# Sheet1.net
KiCad netlist of a schematic drawn in Altium Designer
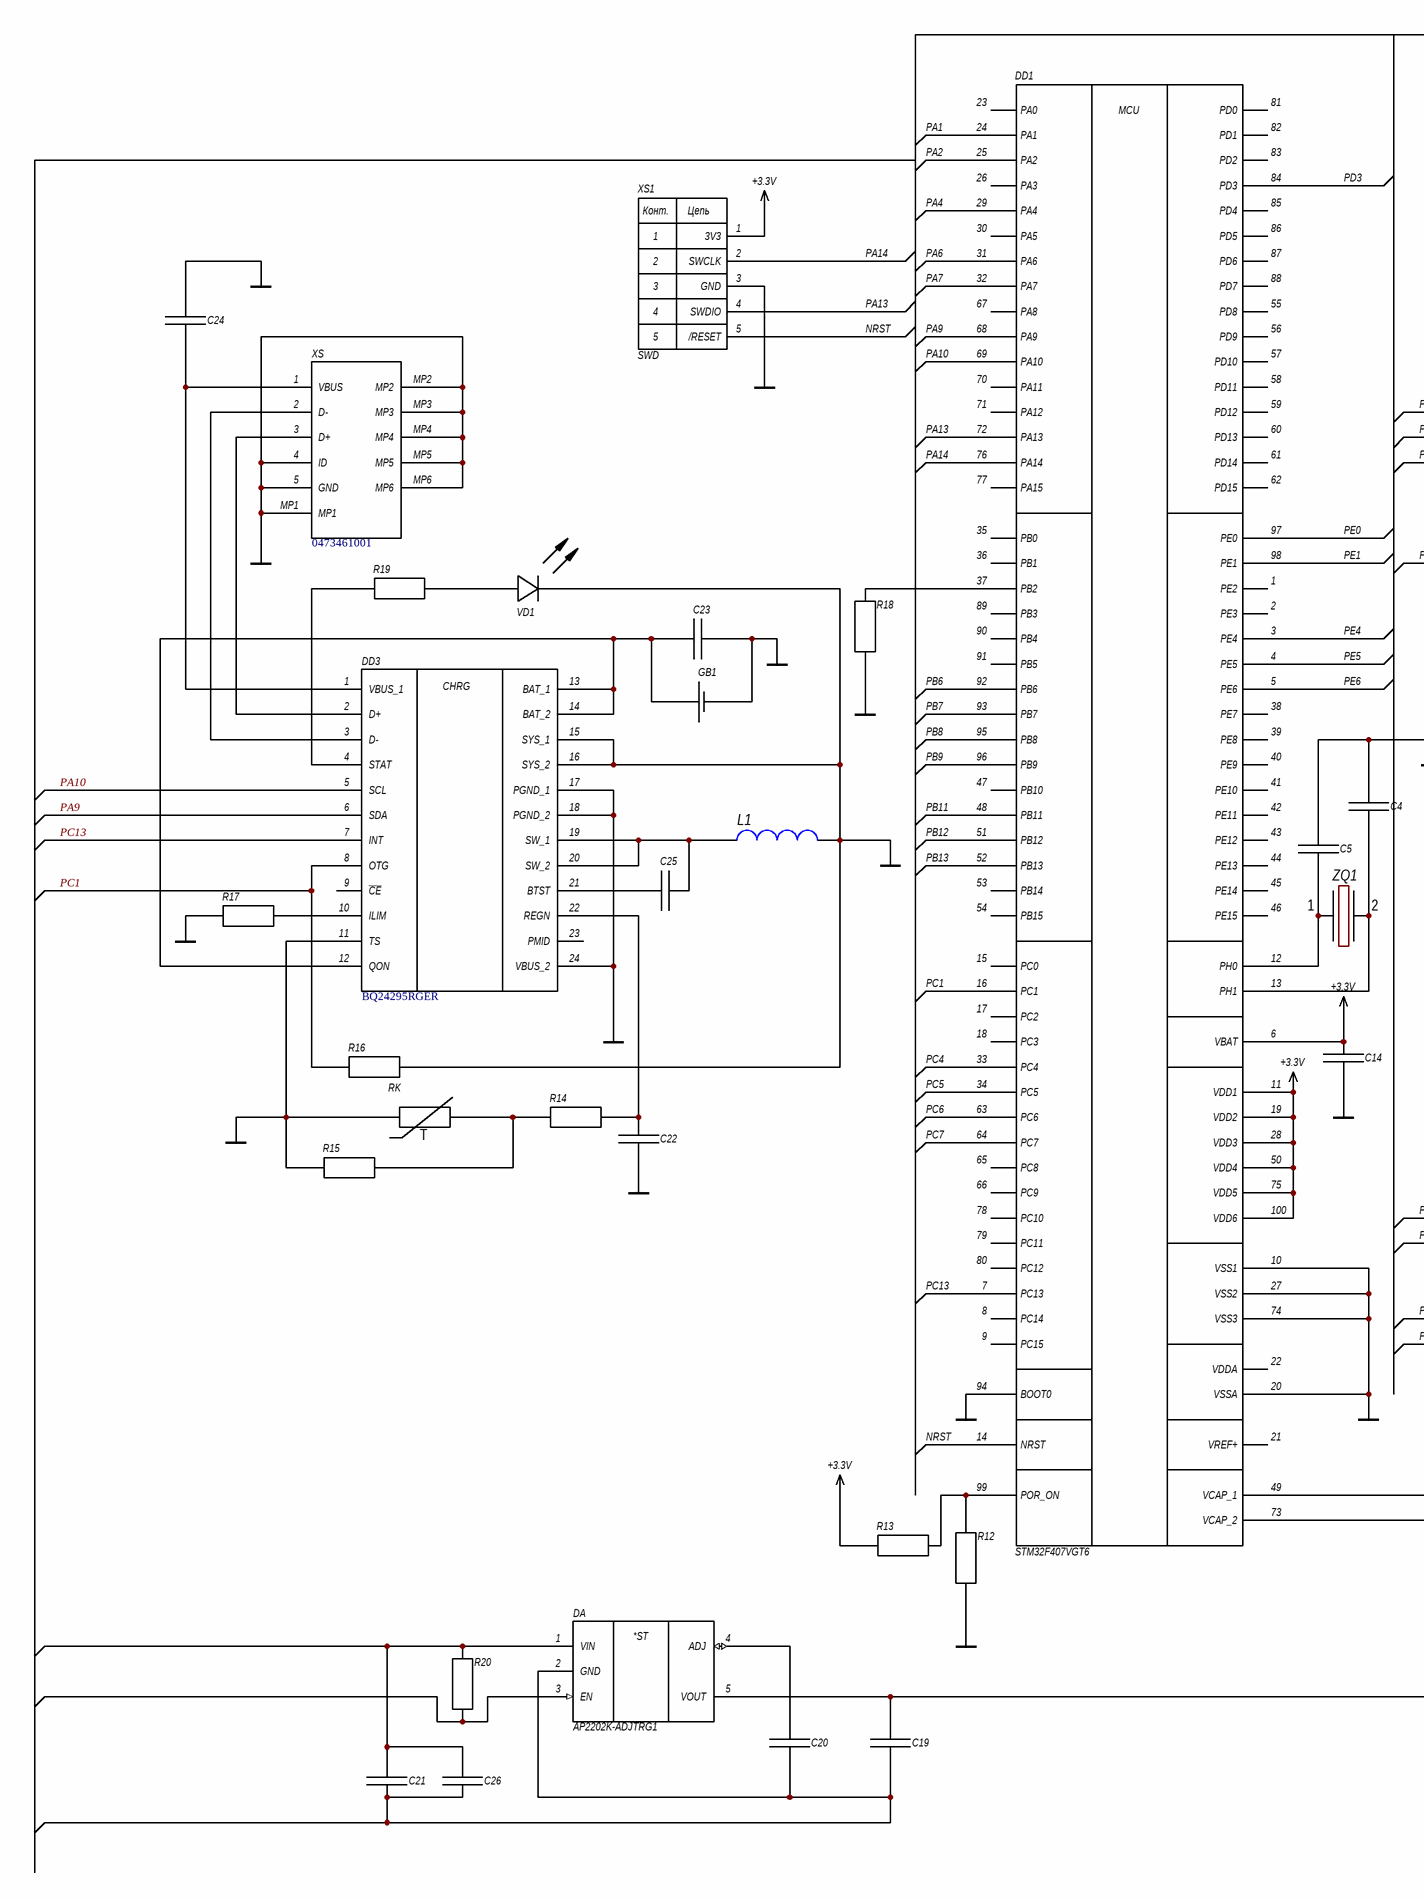
[diagram p0: Sheet1.SchDoc, left]
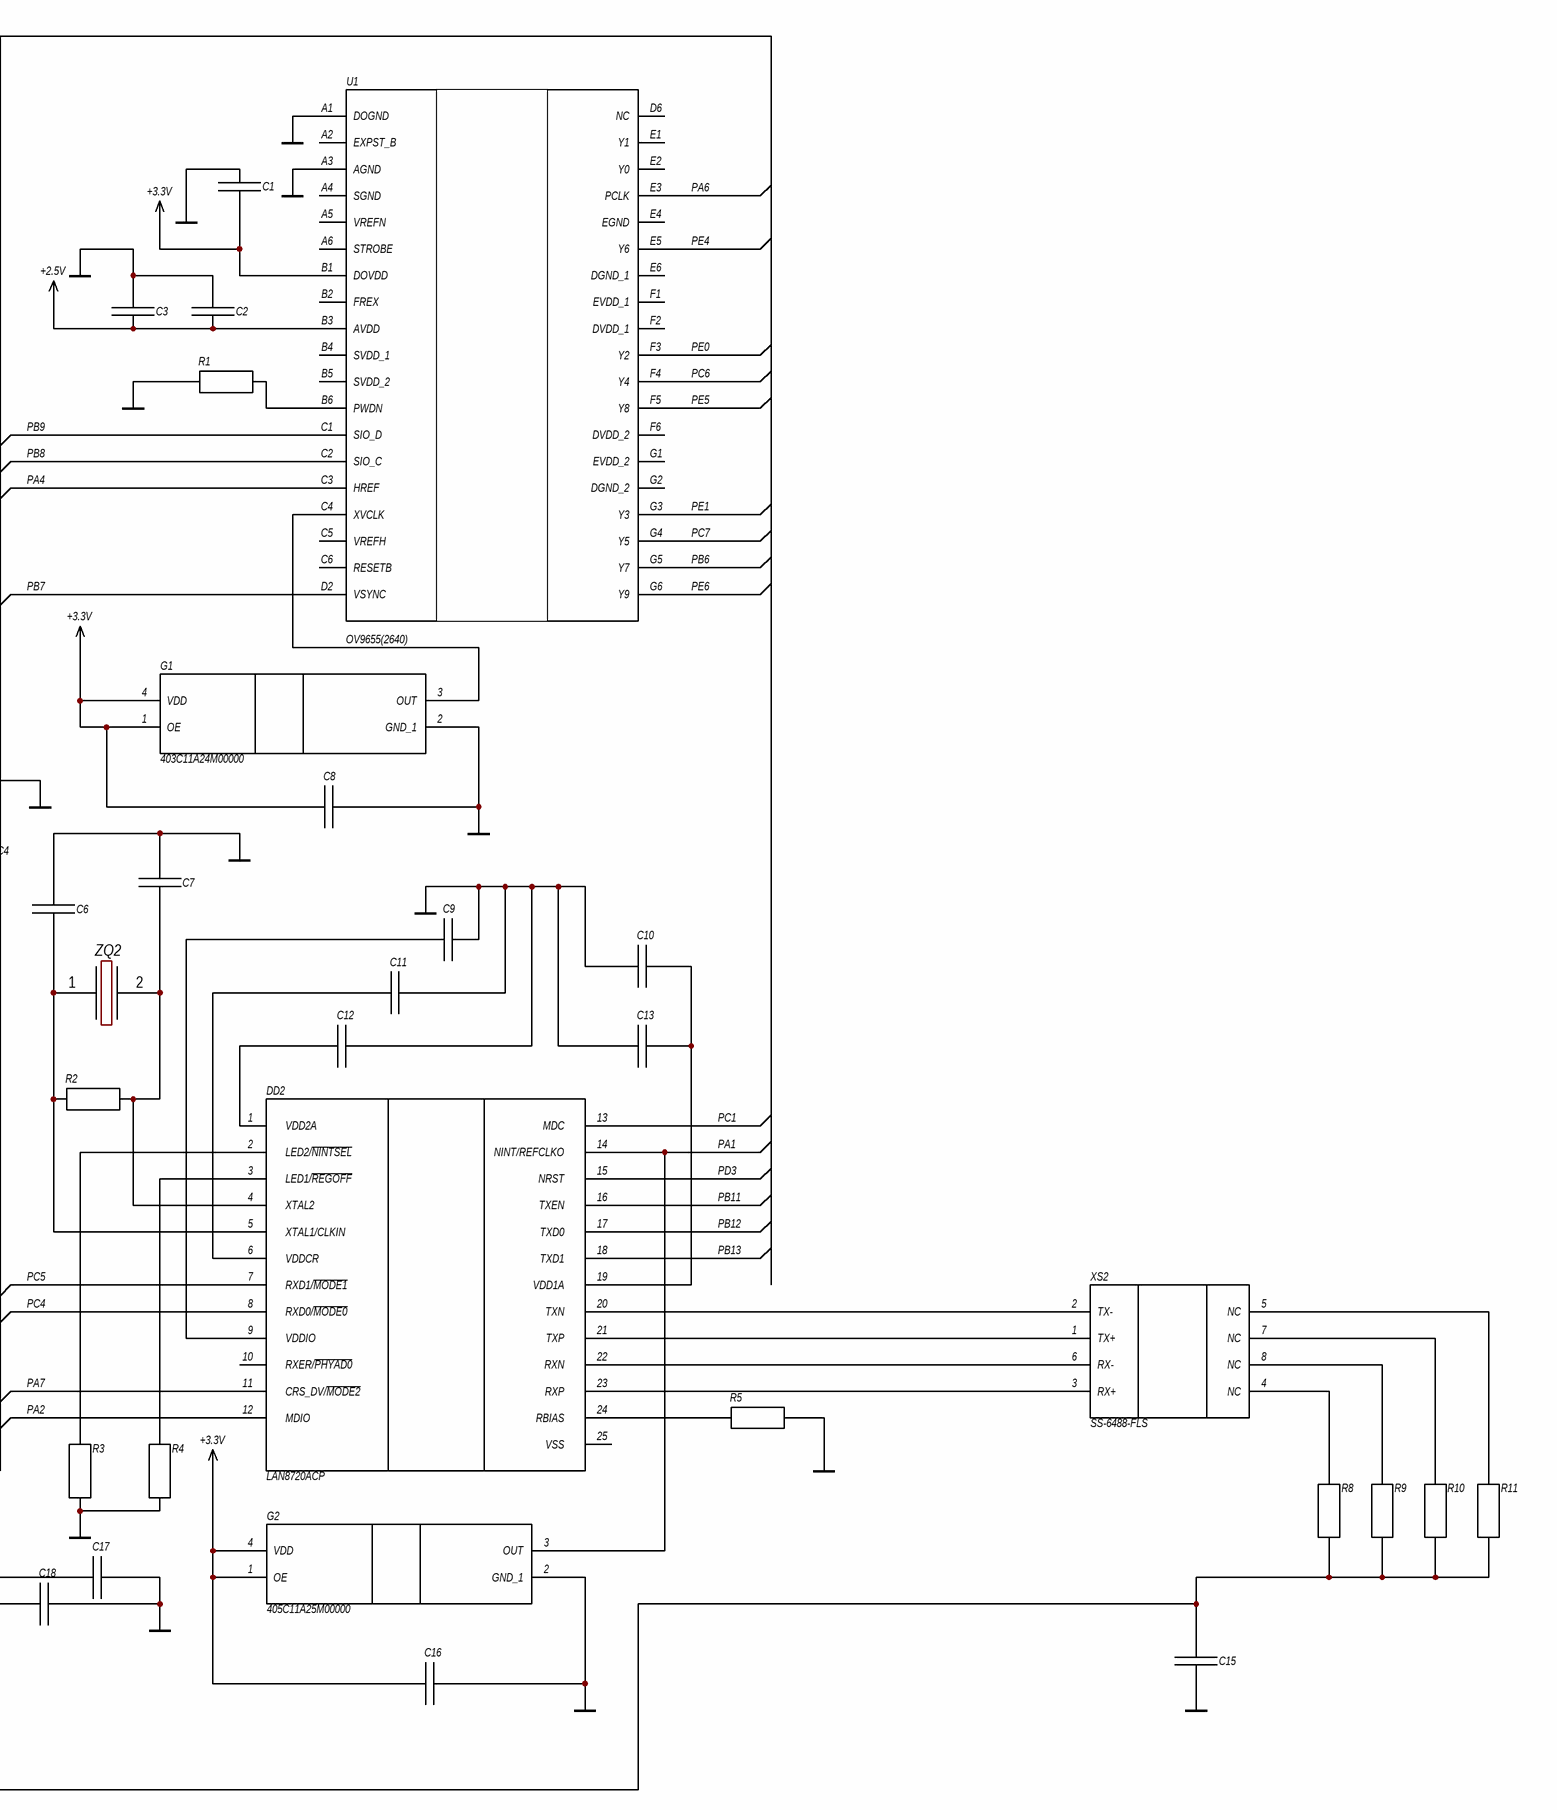
[diagram p1: Sheet1.SchDoc, right]

(export (version "E")
  (design (tool "Eeschema 10.0.6"))
  (components
    (comp (ref "C1")
      (value "~")
      (footprint "0805 (Capacitor)")
      (libsource (lib "SamacSys") (part "Condensator"))
    )
    (comp (ref "C2")
      (value "~")
      (footprint "0805 (Capacitor)")
      (libsource (lib "SamacSys") (part "Condensator"))
    )
    (comp (ref "C3")
      (value "~")
      (footprint "0805 (Capacitor)")
      (libsource (lib "SamacSys") (part "Condensator"))
    )
    (comp (ref "C4")
      (value "~")
      (footprint "0805 (Capacitor)")
      (libsource (lib "SamacSys") (part "Condensator"))
    )
    (comp (ref "C5")
      (value "~")
      (footprint "0805 (Capacitor)")
      (libsource (lib "SamacSys") (part "Condensator"))
    )
    (comp (ref "C6")
      (value "~")
      (footprint "0805 (Capacitor)")
      (libsource (lib "SamacSys") (part "Condensator"))
    )
    (comp (ref "C7")
      (value "~")
      (footprint "0805 (Capacitor)")
      (libsource (lib "SamacSys") (part "Condensator"))
    )
    (comp (ref "C8")
      (value "~")
      (footprint "0805 (Capacitor)")
      (libsource (lib "SamacSys") (part "Condensator"))
    )
    (comp (ref "C9")
      (value "~")
      (footprint "0805 (Capacitor)")
      (libsource (lib "SamacSys") (part "Condensator"))
    )
    (comp (ref "C10")
      (value "~")
      (footprint "0805 (Capacitor)")
      (libsource (lib "SamacSys") (part "Condensator"))
    )
    (comp (ref "C11")
      (value "~")
      (footprint "0805 (Capacitor)")
      (libsource (lib "SamacSys") (part "Condensator"))
    )
    (comp (ref "C12")
      (value "~")
      (footprint "0805 (Capacitor)")
      (libsource (lib "SamacSys") (part "Condensator"))
    )
    (comp (ref "C13")
      (value "~")
      (footprint "0805 (Capacitor)")
      (libsource (lib "SamacSys") (part "Condensator"))
    )
    (comp (ref "C14")
      (value "~")
      (footprint "0805 (Capacitor)")
      (libsource (lib "SamacSys") (part "Condensator"))
    )
    (comp (ref "C15")
      (value "~")
      (footprint "0805 (Capacitor)")
      (libsource (lib "SamacSys") (part "Condensator"))
    )
    (comp (ref "C16")
      (value "~")
      (footprint "0805 (Capacitor)")
      (libsource (lib "SamacSys") (part "Condensator"))
    )
    (comp (ref "C17")
      (value "~")
      (footprint "0805 (Capacitor)")
      (libsource (lib "SamacSys") (part "Condensator"))
    )
    (comp (ref "C18")
      (value "~")
      (footprint "0805 (Capacitor)")
      (libsource (lib "SamacSys") (part "Condensator"))
    )
    (comp (ref "C19")
      (value "~")
      (footprint "0805 (Capacitor)")
      (libsource (lib "SamacSys") (part "Condensator"))
    )
    (comp (ref "C20")
      (value "~")
      (footprint "0805 (Capacitor)")
      (libsource (lib "SamacSys") (part "Condensator"))
    )
    (comp (ref "C21")
      (value "~")
      (footprint "0805 (Capacitor)")
      (libsource (lib "SamacSys") (part "Condensator"))
    )
    (comp (ref "C22")
      (value "~")
      (footprint "0805 (Capacitor)")
      (libsource (lib "SamacSys") (part "Condensator"))
    )
    (comp (ref "C23")
      (value "~")
      (footprint "0805 (Capacitor)")
      (libsource (lib "SamacSys") (part "Condensator"))
    )
    (comp (ref "C24")
      (value "~")
      (footprint "0805 (Capacitor)")
      (libsource (lib "SamacSys") (part "Condensator"))
    )
    (comp (ref "C25")
      (value "~")
      (footprint "0805 (Capacitor)")
      (libsource (lib "SamacSys") (part "Condensator"))
    )
    (comp (ref "C26")
      (value "~")
      (footprint "0805 (Capacitor)")
      (libsource (lib "SamacSys") (part "Condensator"))
    )
    (comp (ref "DA")
      (value "AP2202K-ADJTRG1")
      (footprint "SOT95P280X145-5N")
      (description "Power Supply")
      (fields (field (name "MOUSER PART NUMBER") "621-AP2202K-ADJTRG1"))
      (libsource (lib "SamacSys") (part "AP2202K-ADJTRG1"))
    )
    (comp (ref "DD1")
      (value "STM32F407VGT6")
      (footprint "QFP50P1600X1600X160-100N")
      (description "Integrated Circuit")
      (fields (field (name "MOUSER PART NUMBER") "511-STM32F407VGT6"))
      (libsource (lib "SamacSys") (part "STM32F407VGT6"))
    )
    (comp (ref "DD2")
      (value "LAN8720ACP")
      (footprint "SamacSys:QFN50P400X400X100-25N-D")
      (description "Integrated Circuit")
      (libsource (lib "SamacSys") (part "LAN8720ACP"))
    )
    (comp (ref "DD3")
      (value "BQ24295RGER")
      (footprint "SamacSys:QFN50P400X400X100-25N-D")
      (description "Integrated Circuit")
      (fields (field (name "MOUSER PART NUMBER") "595-BQ24295RGER"))
      (libsource (lib "SamacSys") (part "BQ24295RGER"))
    )
    (comp (ref "G1")
      (value "403C11A24M00000")
      (footprint "403C11A20M00000")
      (description "Crystal or Oscillator")
      (fields (field (name "MOUSER PART NUMBER") "774-403C11A24M00000"))
      (libsource (lib "SamacSys") (part "403C11A24M00000"))
    )
    (comp (ref "G2")
      (value "405C11A25M00000")
      (footprint "405C11A25M00000")
      (description "Crystal or Oscillator")
      (fields (field (name "MOUSER PART NUMBER") "774-405C11A25M00000"))
      (libsource (lib "SamacSys") (part "405C11A25M00000"))
    )
    (comp (ref "GB1") (value "~") (footprint "Battery") (libsource (lib "SamacSys") (part "Battery")))
    (comp (ref "L1")
      (value "~")
      (footprint "IND: SDR0604")
      (fields
        (field (name "MANUFACTURER") "Murata Electronics")
        (field (name "PARTNUMBER") "LQM18FN100M00D")
        (field (name "VALUEMANUFACTURERPARTNUMBER") "Fixed inductor, , , 0603, 50mA, -55...+125°C")
      )
      (libsource (lib "SamacSys") (part "Inductor_0603"))
    )
    (comp (ref "R1") (value "~") (footprint "0805 (Resistor)") (libsource (lib "SamacSys") (part "Resistor")))
    (comp (ref "R2") (value "~") (footprint "0805 (Resistor)") (libsource (lib "SamacSys") (part "Resistor")))
    (comp (ref "R3") (value "~") (footprint "0805 (Resistor)") (libsource (lib "SamacSys") (part "Resistor")))
    (comp (ref "R4") (value "~") (footprint "0805 (Resistor)") (libsource (lib "SamacSys") (part "Resistor")))
    (comp (ref "R5") (value "~") (footprint "0805 (Resistor)") (libsource (lib "SamacSys") (part "Resistor")))
    (comp (ref "R8") (value "~") (footprint "0805 (Resistor)") (libsource (lib "SamacSys") (part "Resistor")))
    (comp (ref "R9") (value "~") (footprint "0805 (Resistor)") (libsource (lib "SamacSys") (part "Resistor")))
    (comp (ref "R10")
      (value "~")
      (footprint "0805 (Resistor)")
      (libsource (lib "SamacSys") (part "Resistor"))
    )
    (comp (ref "R11")
      (value "~")
      (footprint "0805 (Resistor)")
      (libsource (lib "SamacSys") (part "Resistor"))
    )
    (comp (ref "R12")
      (value "~")
      (footprint "0805 (Resistor)")
      (libsource (lib "SamacSys") (part "Resistor"))
    )
    (comp (ref "R13")
      (value "~")
      (footprint "0805 (Resistor)")
      (libsource (lib "SamacSys") (part "Resistor"))
    )
    (comp (ref "R14")
      (value "~")
      (footprint "0805 (Resistor)")
      (libsource (lib "SamacSys") (part "Resistor"))
    )
    (comp (ref "R15")
      (value "~")
      (footprint "0805 (Resistor)")
      (libsource (lib "SamacSys") (part "Resistor"))
    )
    (comp (ref "R16")
      (value "~")
      (footprint "0805 (Resistor)")
      (libsource (lib "SamacSys") (part "Resistor"))
    )
    (comp (ref "R17")
      (value "~")
      (footprint "0805 (Resistor)")
      (libsource (lib "SamacSys") (part "Resistor"))
    )
    (comp (ref "R18")
      (value "~")
      (footprint "0805 (Resistor)")
      (libsource (lib "SamacSys") (part "Resistor"))
    )
    (comp (ref "R19")
      (value "~")
      (footprint "0805 (Resistor)")
      (libsource (lib "SamacSys") (part "Resistor"))
    )
    (comp (ref "R20")
      (value "~")
      (footprint "0805 (Resistor)")
      (libsource (lib "SamacSys") (part "Resistor"))
    )
    (comp (ref "RK")
      (value "~")
      (footprint "0805 (Resistor)")
      (libsource (lib "SamacSys") (part "Resistor_termo"))
    )
    (comp (ref "U1")
      (value "OV9655(2640)")
      (footprint "BGA38C80P6X7_572X628X96")
      (description "Integrated Circuit")
      (fields (field (name "MANUFACTURER_PART_NUMBER") "OV2640-VL9A"))
      (libsource (lib "SamacSys") (part "OV2640-VL9A"))
    )
    (comp (ref "VD1")
      (value "~")
      (footprint "LED")
      (fields (field (name "VALUEMANUFACTURERPARTNUMBER") "LED, Green, *, *, *, -55...+150°C"))
      (libsource (lib "SamacSys") (part "LED_single"))
    )
    (comp (ref "XS")
      (value "0473461001")
      (footprint "0473461001")
      (description "Connector")
      (libsource (lib "SamacSys") (part "0473461001"))
    )
    (comp (ref "XS1") (value "SWD") (footprint "SWD") (libsource (lib "SamacSys") (part "SWD")))
    (comp (ref "XS2")
      (value "SS-6488-FLS")
      (footprint "SamacSys:SS6488FLS")
      (description "Connector")
      (fields (field (name "MOUSER PART NUMBER") "530-SS-6488-FLS"))
      (libsource (lib "SamacSys") (part "SS-6488-FLS"))
    )
    (comp (ref "ZQ1")
      (value "~")
      (footprint "OSC: 2016")
      (fields
        (field (name "MANUFACTURER") "Murata Electronics")
        (field (name "PARTNUMBER") "XRCGB25M000F0L00R0")
        (field (name "VALUEMANUFACTURERPARTNUMBER") "Crystal, , 6pF, ±50ppm, case 2016, -30...+85°C")
      )
      (libsource (lib "SamacSys") (part "Crystal_2016"))
    )
    (comp (ref "ZQ2")
      (value "~")
      (footprint "OSC: 2016")
      (fields
        (field (name "MANUFACTURER") "Murata Electronics")
        (field (name "PARTNUMBER") "XRCGB25M000F0L00R0")
        (field (name "VALUEMANUFACTURERPARTNUMBER") "Crystal, , 6pF, ±50ppm, case 2016, -30...+85°C")
      )
      (libsource (lib "SamacSys") (part "Crystal_2016"))
    )
  )
  (nets
    (net (code "1") (name "+2.5V") (class "Default")
      (node (ref "C2") (pin "2") (pinfunction "2_2") (pintype "passive"))
      (node (ref "C3") (pin "2") (pinfunction "2_2") (pintype "passive"))
      (node (ref "U1") (pin "B3") (pinfunction "AVDD_B3") (pintype "passive"))
    )
    (net (code "2") (name "+3.3V") (class "Default")
      (node (ref "C1") (pin "2") (pinfunction "2_2") (pintype "passive"))
      (node (ref "C14") (pin "1") (pinfunction "1_1") (pintype "passive"))
      (node (ref "C16") (pin "1") (pinfunction "1_1") (pintype "passive"))
      (node (ref "C8") (pin "1") (pinfunction "1_1") (pintype "passive"))
      (node (ref "DD1") (pin "100") (pinfunction "VDD6_100") (pintype "passive"))
      (node (ref "DD1") (pin "11") (pinfunction "VDD1_11") (pintype "passive"))
      (node (ref "DD1") (pin "19") (pinfunction "VDD2_19") (pintype "passive"))
      (node (ref "DD1") (pin "28") (pinfunction "VDD3_28") (pintype "passive"))
      (node (ref "DD1") (pin "50") (pinfunction "VDD4_50") (pintype "passive"))
      (node (ref "DD1") (pin "6") (pinfunction "VBAT_6") (pintype "passive"))
      (node (ref "DD1") (pin "75") (pinfunction "VDD5_75") (pintype "passive"))
      (node (ref "G1") (pin "1") (pinfunction "OE_1") (pintype "passive"))
      (node (ref "G1") (pin "4") (pinfunction "VDD_4") (pintype "passive"))
      (node (ref "G2") (pin "1") (pinfunction "OE_1") (pintype "passive"))
      (node (ref "G2") (pin "4") (pinfunction "VDD_4") (pintype "passive"))
      (node (ref "R13") (pin "2") (pinfunction "2_2") (pintype "passive"))
      (node (ref "U1") (pin "B1") (pinfunction "DOVDD_B1") (pintype "passive"))
      (node (ref "XS1") (pin "1") (pinfunction "3V3_1") (pintype "passive"))
    )
    (net (code "3") (name "/GND") (class "Default")
      (node (ref "C1") (pin "1") (pinfunction "1_1") (pintype "passive"))
      (node (ref "C10") (pin "1") (pinfunction "1_1") (pintype "passive"))
      (node (ref "C11") (pin "2") (pinfunction "2_2") (pintype "passive"))
      (node (ref "C12") (pin "2") (pinfunction "2_2") (pintype "passive"))
      (node (ref "C13") (pin "1") (pinfunction "1_1") (pintype "passive"))
      (node (ref "C14") (pin "2") (pinfunction "2_2") (pintype "passive"))
      (node (ref "C15") (pin "1") (pinfunction "1_1") (pintype "passive"))
      (node (ref "C16") (pin "2") (pinfunction "2_2") (pintype "passive"))
      (node (ref "C17") (pin "2") (pinfunction "2_2") (pintype "passive"))
      (node (ref "C18") (pin "2") (pinfunction "2_2") (pintype "passive"))
      (node (ref "C2") (pin "1") (pinfunction "1_1") (pintype "passive"))
      (node (ref "C22") (pin "2") (pinfunction "2_2") (pintype "passive"))
      (node (ref "C23") (pin "2") (pinfunction "2_2") (pintype "passive"))
      (node (ref "C24") (pin "2") (pinfunction "2_2") (pintype "passive"))
      (node (ref "C3") (pin "1") (pinfunction "1_1") (pintype "passive"))
      (node (ref "C4") (pin "1") (pinfunction "1_1") (pintype "passive"))
      (node (ref "C5") (pin "1") (pinfunction "1_1") (pintype "passive"))
      (node (ref "C6") (pin "1") (pinfunction "1_1") (pintype "passive"))
      (node (ref "C7") (pin "1") (pinfunction "1_1") (pintype "passive"))
      (node (ref "C8") (pin "2") (pinfunction "2_2") (pintype "passive"))
      (node (ref "C9") (pin "2") (pinfunction "2_2") (pintype "passive"))
      (node (ref "DD1") (pin "10") (pinfunction "VSS1_10") (pintype "passive"))
      (node (ref "DD1") (pin "20") (pinfunction "VSSA_20") (pintype "passive"))
      (node (ref "DD1") (pin "27") (pinfunction "VSS2_27") (pintype "passive"))
      (node (ref "DD1") (pin "74") (pinfunction "VSS3_74") (pintype "passive"))
      (node (ref "DD1") (pin "94") (pinfunction "BOOT0_94") (pintype "passive"))
      (node (ref "DD3") (pin "11") (pinfunction "TS_11") (pintype "passive"))
      (node (ref "DD3") (pin "15") (pinfunction "SYS_1_15") (pintype "passive"))
      (node (ref "DD3") (pin "16") (pinfunction "SYS_2_16") (pintype "passive"))
      (node (ref "DD3") (pin "17") (pinfunction "PGND_1_17") (pintype "passive"))
      (node (ref "DD3") (pin "18") (pinfunction "PGND_2_18") (pintype "passive"))
      (node (ref "DD3") (pin "24") (pinfunction "VBUS_2_24") (pintype "passive"))
      (node (ref "G1") (pin "2") (pinfunction "GND_1_2") (pintype "passive"))
      (node (ref "G2") (pin "2") (pinfunction "GND_1_2") (pintype "passive"))
      (node (ref "GB1") (pin "2") (pintype "passive"))
      (node (ref "L1") (pin "1") (pinfunction "1_1") (pintype "passive"))
      (node (ref "R1") (pin "1") (pinfunction "1_1") (pintype "passive"))
      (node (ref "R12") (pin "1") (pinfunction "1_1") (pintype "passive"))
      (node (ref "R15") (pin "1") (pinfunction "1_1") (pintype "passive"))
      (node (ref "R16") (pin "2") (pinfunction "2_2") (pintype "passive"))
      (node (ref "R17") (pin "1") (pinfunction "1_1") (pintype "passive"))
      (node (ref "R18") (pin "1") (pinfunction "1_1") (pintype "passive"))
      (node (ref "R3") (pin "1") (pinfunction "1_1") (pintype "passive"))
      (node (ref "R4") (pin "1") (pinfunction "1_1") (pintype "passive"))
      (node (ref "R5") (pin "2") (pinfunction "2_2") (pintype "passive"))
      (node (ref "RK") (pin "1") (pinfunction "1_1") (pintype "passive"))
      (node (ref "U1") (pin "A1") (pinfunction "DOGND_A1") (pintype "passive"))
      (node (ref "U1") (pin "A3") (pinfunction "AGND_A3") (pintype "passive"))
      (node (ref "VD1") (pin "2") (pinfunction "C_2") (pintype "passive"))
      (node (ref "XS") (pin "4") (pinfunction "ID_4") (pintype "passive"))
      (node (ref "XS") (pin "5") (pinfunction "GND_5") (pintype "passive"))
      (node (ref "XS") (pin "MP1") (pinfunction "MP1_MP1") (pintype "passive"))
      (node (ref "XS") (pin "MP2") (pinfunction "MP2_MP2") (pintype "passive"))
      (node (ref "XS") (pin "MP3") (pinfunction "MP3_MP3") (pintype "passive"))
      (node (ref "XS") (pin "MP4") (pinfunction "MP4_MP4") (pintype "passive"))
      (node (ref "XS") (pin "MP5") (pinfunction "MP5_MP5") (pintype "passive"))
      (node (ref "XS") (pin "MP6") (pinfunction "MP6_MP6") (pintype "passive"))
      (node (ref "XS1") (pin "3") (pinfunction "GND_3") (pintype "passive"))
    )
    (net (code "4") (name "/NRST") (class "Default")
      (node (ref "DD1") (pin "14") (pinfunction "NRST_14") (pintype "passive"))
      (node (ref "XS1") (pin "5") (pinfunction "/RESET_5") (pintype "passive"))
    )
    (net (code "5") (name "/PA1") (class "Default")
      (node (ref "DD1") (pin "24") (pinfunction "PA1_24") (pintype "passive"))
      (node (ref "DD2") (pin "14") (pinfunction "NINT/REFCLKO_14") (pintype "passive"))
      (node (ref "G2") (pin "3") (pinfunction "OUT_3") (pintype "passive"))
    )
    (net (code "6") (name "/PA2") (class "Default")
      (node (ref "DD1") (pin "25") (pinfunction "PA2_25") (pintype "passive"))
      (node (ref "DD2") (pin "12") (pinfunction "MDIO_12") (pintype "passive"))
    )
    (net (code "7") (name "/PA4") (class "Default")
      (node (ref "DD1") (pin "29") (pinfunction "PA4_29") (pintype "passive"))
      (node (ref "U1") (pin "C3") (pinfunction "HREF_C3") (pintype "passive"))
    )
    (net (code "8") (name "/PA6") (class "Default")
      (node (ref "DD1") (pin "31") (pinfunction "PA6_31") (pintype "passive"))
      (node (ref "U1") (pin "E3") (pinfunction "PCLK_E3") (pintype "passive"))
    )
    (net (code "9") (name "/PA7") (class "Default")
      (node (ref "DD1") (pin "32") (pinfunction "PA7_32") (pintype "passive"))
      (node (ref "DD2") (pin "11") (pinfunction "CRS_DV/~{MODE2}_11") (pintype "passive"))
    )
    (net (code "10") (name "/PA9") (class "Default")
      (node (ref "DD1") (pin "68") (pinfunction "PA9_68") (pintype "passive"))
      (node (ref "DD3") (pin "6") (pinfunction "SDA_6") (pintype "passive"))
    )
    (net (code "11") (name "/PA10") (class "Default")
      (node (ref "DD1") (pin "69") (pinfunction "PA10_69") (pintype "passive"))
      (node (ref "DD3") (pin "5") (pinfunction "SCL_5") (pintype "passive"))
    )
    (net (code "12") (name "/PA13") (class "Default")
      (node (ref "DD1") (pin "72") (pinfunction "PA13_72") (pintype "passive"))
      (node (ref "XS1") (pin "4") (pinfunction "SWDIO_4") (pintype "passive"))
    )
    (net (code "13") (name "/PA14") (class "Default")
      (node (ref "DD1") (pin "76") (pinfunction "PA14_76") (pintype "passive"))
      (node (ref "XS1") (pin "2") (pinfunction "SWCLK_2") (pintype "passive"))
    )
    (net (code "14") (name "/PB6") (class "Default")
      (node (ref "DD1") (pin "92") (pinfunction "PB6_92") (pintype "passive"))
      (node (ref "U1") (pin "G5") (pinfunction "Y7_G5") (pintype "passive"))
    )
    (net (code "15") (name "/PB7") (class "Default")
      (node (ref "DD1") (pin "93") (pinfunction "PB7_93") (pintype "passive"))
      (node (ref "U1") (pin "D2") (pinfunction "VSYNC_D2") (pintype "passive"))
    )
    (net (code "16") (name "/PB8") (class "Default")
      (node (ref "DD1") (pin "95") (pinfunction "PB8_95") (pintype "passive"))
      (node (ref "U1") (pin "C2") (pinfunction "SIO_C_C2") (pintype "passive"))
    )
    (net (code "17") (name "/PB9") (class "Default")
      (node (ref "DD1") (pin "96") (pinfunction "PB9_96") (pintype "passive"))
      (node (ref "U1") (pin "C1") (pinfunction "SIO_D_C1") (pintype "passive"))
    )
    (net (code "18") (name "/PB11") (class "Default")
      (node (ref "DD1") (pin "48") (pinfunction "PB11_48") (pintype "passive"))
      (node (ref "DD2") (pin "16") (pinfunction "TXEN_16") (pintype "passive"))
    )
    (net (code "19") (name "/PB12") (class "Default")
      (node (ref "DD1") (pin "51") (pinfunction "PB12_51") (pintype "passive"))
      (node (ref "DD2") (pin "17") (pinfunction "TXD0_17") (pintype "passive"))
    )
    (net (code "20") (name "/PB13") (class "Default")
      (node (ref "DD1") (pin "52") (pinfunction "PB13_52") (pintype "passive"))
      (node (ref "DD2") (pin "18") (pinfunction "TXD1_18") (pintype "passive"))
    )
    (net (code "21") (name "/PC1") (class "Default")
      (node (ref "DD1") (pin "16") (pinfunction "PC1_16") (pintype "passive"))
      (node (ref "DD2") (pin "13") (pinfunction "MDC_13") (pintype "passive"))
      (node (ref "DD3") (pin "8") (pinfunction "OTG_8") (pintype "passive"))
      (node (ref "R16") (pin "1") (pinfunction "1_1") (pintype "passive"))
    )
    (net (code "22") (name "/PC4") (class "Default")
      (node (ref "DD1") (pin "33") (pinfunction "PC4_33") (pintype "passive"))
      (node (ref "DD2") (pin "8") (pinfunction "RXD0/~{MODE0}_8") (pintype "passive"))
    )
    (net (code "23") (name "/PC5") (class "Default")
      (node (ref "DD1") (pin "34") (pinfunction "PC5_34") (pintype "passive"))
      (node (ref "DD2") (pin "7") (pinfunction "RXD1/~{MODE1}_7") (pintype "passive"))
    )
    (net (code "24") (name "/PC6") (class "Default")
      (node (ref "DD1") (pin "63") (pinfunction "PC6_63") (pintype "passive"))
      (node (ref "U1") (pin "F4") (pinfunction "Y4_F4") (pintype "passive"))
    )
    (net (code "25") (name "/PC7") (class "Default")
      (node (ref "DD1") (pin "64") (pinfunction "PC7_64") (pintype "passive"))
      (node (ref "U1") (pin "G4") (pinfunction "Y5_G4") (pintype "passive"))
    )
    (net (code "26") (name "/PC13") (class "Default")
      (node (ref "DD1") (pin "7") (pinfunction "PC13_7") (pintype "passive"))
      (node (ref "DD3") (pin "7") (pinfunction "INT_7") (pintype "passive"))
    )
    (net (code "27") (name "/PD3") (class "Default")
      (node (ref "DD1") (pin "84") (pinfunction "PD3_84") (pintype "passive"))
      (node (ref "DD2") (pin "15") (pinfunction "NRST_15") (pintype "passive"))
    )
    (net (code "28") (name "/PE0") (class "Default")
      (node (ref "DD1") (pin "97") (pinfunction "PE0_97") (pintype "passive"))
      (node (ref "U1") (pin "F3") (pinfunction "Y2_F3") (pintype "passive"))
    )
    (net (code "29") (name "/PE1") (class "Default")
      (node (ref "DD1") (pin "98") (pinfunction "PE1_98") (pintype "passive"))
      (node (ref "U1") (pin "G3") (pinfunction "Y3_G3") (pintype "passive"))
    )
    (net (code "30") (name "/PE4") (class "Default")
      (node (ref "DD1") (pin "3") (pinfunction "PE4_3") (pintype "passive"))
      (node (ref "U1") (pin "E5") (pinfunction "Y6_E5") (pintype "passive"))
    )
    (net (code "31") (name "/PE5") (class "Default")
      (node (ref "DD1") (pin "4") (pinfunction "PE5_4") (pintype "passive"))
      (node (ref "U1") (pin "F5") (pinfunction "Y8_F5") (pintype "passive"))
    )
    (net (code "32") (name "/PE6") (class "Default")
      (node (ref "DD1") (pin "5") (pinfunction "PE6_5") (pintype "passive"))
      (node (ref "U1") (pin "G6") (pinfunction "Y9_G6") (pintype "passive"))
    )
    (net (code "33") (name "Net-(DA-ADJ)") (class "Default")
      (node (ref "C20") (pin "1") (pinfunction "1_1") (pintype "passive"))
      (node (ref "DA") (pin "4") (pinfunction "ADJ_4") (pintype "bidirectional"))
    )
    (net (code "34") (name "Net-(DA-EN)") (class "Default")
      (node (ref "DA") (pin "3") (pinfunction "EN_3") (pintype "input"))
      (node (ref "R20") (pin "1") (pinfunction "1_1") (pintype "passive"))
    )
    (net (code "35") (name "Net-(DA-GND)") (class "Default")
      (node (ref "C19") (pin "2") (pinfunction "2_2") (pintype "passive"))
      (node (ref "C20") (pin "2") (pinfunction "2_2") (pintype "passive"))
      (node (ref "C21") (pin "1") (pinfunction "1_1") (pintype "passive"))
      (node (ref "C26") (pin "1") (pinfunction "1_1") (pintype "passive"))
      (node (ref "DA") (pin "2") (pinfunction "GND_2") (pintype "power_in"))
    )
    (net (code "36") (name "Net-(DA-VIN)") (class "Default")
      (node (ref "C21") (pin "2") (pinfunction "2_2") (pintype "passive"))
      (node (ref "C26") (pin "2") (pinfunction "2_2") (pintype "passive"))
      (node (ref "DA") (pin "1") (pinfunction "VIN_1") (pintype "power_in"))
      (node (ref "R20") (pin "2") (pinfunction "2_2") (pintype "passive"))
    )
    (net (code "37") (name "Net-(DA-VOUT)") (class "Default")
      (node (ref "C15") (pin "2") (pinfunction "2_2") (pintype "passive"))
      (node (ref "C19") (pin "1") (pinfunction "1_1") (pintype "passive"))
      (node (ref "DA") (pin "5") (pinfunction "VOUT_5") (pintype "power_in"))
      (node (ref "R10") (pin "1") (pinfunction "1_1") (pintype "passive"))
      (node (ref "R11") (pin "1") (pinfunction "1_1") (pintype "passive"))
      (node (ref "R8") (pin "1") (pinfunction "1_1") (pintype "passive"))
      (node (ref "R9") (pin "1") (pinfunction "1_1") (pintype "passive"))
    )
    (net (code "38") (name "Net-(DD1-PB2)") (class "Default")
      (node (ref "DD1") (pin "37") (pinfunction "PB2_37") (pintype "passive"))
      (node (ref "R18") (pin "2") (pinfunction "2_2") (pintype "passive"))
    )
    (net (code "39") (name "Net-(DD1-PH0)") (class "Default")
      (node (ref "C5") (pin "2") (pinfunction "2_2") (pintype "passive"))
      (node (ref "DD1") (pin "12") (pinfunction "PH0_12") (pintype "passive"))
      (node (ref "ZQ1") (pin "1") (pinfunction "1_1") (pintype "passive"))
    )
    (net (code "40") (name "Net-(DD1-PH1)") (class "Default")
      (node (ref "C4") (pin "2") (pinfunction "2_2") (pintype "passive"))
      (node (ref "DD1") (pin "13") (pinfunction "PH1_13") (pintype "passive"))
      (node (ref "ZQ1") (pin "2") (pinfunction "2_2") (pintype "passive"))
    )
    (net (code "41") (name "Net-(DD1-POR_ON)") (class "Default")
      (node (ref "DD1") (pin "99") (pinfunction "POR_ON_99") (pintype "passive"))
      (node (ref "R12") (pin "2") (pinfunction "2_2") (pintype "passive"))
      (node (ref "R13") (pin "1") (pinfunction "1_1") (pintype "passive"))
    )
    (net (code "42") (name "Net-(DD1-VCAP_1)") (class "Default")
      (node (ref "C17") (pin "1") (pinfunction "1_1") (pintype "passive"))
      (node (ref "DD1") (pin "49") (pinfunction "VCAP_1_49") (pintype "passive"))
    )
    (net (code "43") (name "Net-(DD1-VCAP_2)") (class "Default")
      (node (ref "C18") (pin "1") (pinfunction "1_1") (pintype "passive"))
      (node (ref "DD1") (pin "73") (pinfunction "VCAP_2_73") (pintype "passive"))
    )
    (net (code "44") (name "Net-(DD2-LED1{slash}~{REGOFF})") (class "Default")
      (node (ref "DD2") (pin "3") (pinfunction "LED1/~{REGOFF}_3") (pintype "passive"))
      (node (ref "R4") (pin "2") (pinfunction "2_2") (pintype "passive"))
    )
    (net (code "45") (name "Net-(DD2-LED2{slash}~{NINTSEL})") (class "Default")
      (node (ref "DD2") (pin "2") (pinfunction "LED2/~{NINTSEL}_2") (pintype "passive"))
      (node (ref "R3") (pin "2") (pinfunction "2_2") (pintype "passive"))
    )
    (net (code "46") (name "Net-(DD2-RBIAS)") (class "Default")
      (node (ref "DD2") (pin "24") (pinfunction "RBIAS_24") (pintype "passive"))
      (node (ref "R5") (pin "1") (pinfunction "1_1") (pintype "passive"))
    )
    (net (code "47") (name "Net-(DD2-RXN)") (class "Default")
      (node (ref "DD2") (pin "22") (pinfunction "RXN_22") (pintype "passive"))
      (node (ref "XS2") (pin "6") (pinfunction "RX-_6") (pintype "passive"))
    )
    (net (code "48") (name "Net-(DD2-RXP)") (class "Default")
      (node (ref "DD2") (pin "23") (pinfunction "RXP_23") (pintype "passive"))
      (node (ref "XS2") (pin "3") (pinfunction "RX+_3") (pintype "passive"))
    )
    (net (code "49") (name "Net-(DD2-TXN)") (class "Default")
      (node (ref "DD2") (pin "20") (pinfunction "TXN_20") (pintype "passive"))
      (node (ref "XS2") (pin "2") (pinfunction "TX-_2") (pintype "passive"))
    )
    (net (code "50") (name "Net-(DD2-TXP)") (class "Default")
      (node (ref "DD2") (pin "21") (pinfunction "TXP_21") (pintype "passive"))
      (node (ref "XS2") (pin "1") (pinfunction "TX+_1") (pintype "passive"))
    )
    (net (code "51") (name "Net-(DD2-VDD1A)") (class "Default")
      (node (ref "C10") (pin "2") (pinfunction "2_2") (pintype "passive"))
      (node (ref "C13") (pin "2") (pinfunction "2_2") (pintype "passive"))
      (node (ref "DD2") (pin "19") (pinfunction "VDD1A_19") (pintype "passive"))
    )
    (net (code "52") (name "Net-(DD2-VDD2A)") (class "Default")
      (node (ref "C12") (pin "1") (pinfunction "1_1") (pintype "passive"))
      (node (ref "DD2") (pin "1") (pinfunction "VDD2A_1") (pintype "passive"))
    )
    (net (code "53") (name "Net-(DD2-VDDCR)") (class "Default")
      (node (ref "C11") (pin "1") (pinfunction "1_1") (pintype "passive"))
      (node (ref "DD2") (pin "6") (pinfunction "VDDCR_6") (pintype "passive"))
    )
    (net (code "54") (name "Net-(DD2-VDDIO)") (class "Default")
      (node (ref "C9") (pin "1") (pinfunction "1_1") (pintype "passive"))
      (node (ref "DD2") (pin "9") (pinfunction "VDDIO_9") (pintype "passive"))
    )
    (net (code "55") (name "Net-(DD2-XTAL1{slash}CLKIN)") (class "Default")
      (node (ref "C6") (pin "2") (pinfunction "2_2") (pintype "passive"))
      (node (ref "DD2") (pin "5") (pinfunction "XTAL1/CLKIN_5") (pintype "passive"))
      (node (ref "R2") (pin "1") (pinfunction "1_1") (pintype "passive"))
      (node (ref "ZQ2") (pin "1") (pinfunction "1_1") (pintype "passive"))
    )
    (net (code "56") (name "Net-(DD2-XTAL2)") (class "Default")
      (node (ref "C7") (pin "2") (pinfunction "2_2") (pintype "passive"))
      (node (ref "DD2") (pin "4") (pinfunction "XTAL2_4") (pintype "passive"))
      (node (ref "R2") (pin "2") (pinfunction "2_2") (pintype "passive"))
      (node (ref "ZQ2") (pin "2") (pinfunction "2_2") (pintype "passive"))
    )
    (net (code "57") (name "Net-(DD3-BAT_1)") (class "Default")
      (node (ref "C23") (pin "1") (pinfunction "1_1") (pintype "passive"))
      (node (ref "DD3") (pin "12") (pinfunction "QON_12") (pintype "passive"))
      (node (ref "DD3") (pin "13") (pinfunction "BAT_1_13") (pintype "passive"))
      (node (ref "DD3") (pin "14") (pinfunction "BAT_2_14") (pintype "passive"))
      (node (ref "GB1") (pin "1") (pintype "passive"))
    )
    (net (code "58") (name "Net-(DD3-BTST)") (class "Default")
      (node (ref "C25") (pin "2") (pinfunction "2_2") (pintype "passive"))
      (node (ref "DD3") (pin "21") (pinfunction "BTST_21") (pintype "passive"))
    )
    (net (code "59") (name "Net-(DD3-D+)") (class "Default")
      (node (ref "DD3") (pin "2") (pinfunction "D+_2") (pintype "passive"))
      (node (ref "XS") (pin "3") (pinfunction "D+_3") (pintype "passive"))
    )
    (net (code "60") (name "Net-(DD3-D-)") (class "Default")
      (node (ref "DD3") (pin "3") (pinfunction "D-_3") (pintype "passive"))
      (node (ref "XS") (pin "2") (pinfunction "D-_2") (pintype "passive"))
    )
    (net (code "61") (name "Net-(DD3-ILIM)") (class "Default")
      (node (ref "DD3") (pin "10") (pinfunction "ILIM_10") (pintype "passive"))
      (node (ref "R17") (pin "2") (pinfunction "2_2") (pintype "passive"))
    )
    (net (code "62") (name "Net-(DD3-REGN)") (class "Default")
      (node (ref "C22") (pin "1") (pinfunction "1_1") (pintype "passive"))
      (node (ref "DD3") (pin "22") (pinfunction "REGN_22") (pintype "passive"))
      (node (ref "R14") (pin "2") (pinfunction "2_2") (pintype "passive"))
    )
    (net (code "63") (name "Net-(DD3-STAT)") (class "Default")
      (node (ref "DD3") (pin "4") (pinfunction "STAT_4") (pintype "passive"))
      (node (ref "R19") (pin "1") (pinfunction "1_1") (pintype "passive"))
    )
    (net (code "64") (name "Net-(DD3-SW_1)") (class "Default")
      (node (ref "C25") (pin "1") (pinfunction "1_1") (pintype "passive"))
      (node (ref "DD3") (pin "19") (pinfunction "SW_1_19") (pintype "passive"))
      (node (ref "DD3") (pin "20") (pinfunction "SW_2_20") (pintype "passive"))
      (node (ref "L1") (pin "2") (pinfunction "2_2") (pintype "passive"))
    )
    (net (code "65") (name "Net-(DD3-VBUS_1)") (class "Default")
      (node (ref "C24") (pin "1") (pinfunction "1_1") (pintype "passive"))
      (node (ref "DD3") (pin "1") (pinfunction "VBUS_1_1") (pintype "passive"))
      (node (ref "XS") (pin "1") (pinfunction "VBUS_1") (pintype "passive"))
    )
    (net (code "66") (name "Net-(G1-OUT)") (class "Default")
      (node (ref "G1") (pin "3") (pinfunction "OUT_3") (pintype "passive"))
      (node (ref "U1") (pin "C4") (pinfunction "XVCLK_C4") (pintype "passive"))
    )
    (net (code "67") (name "Net-(R8-Pad2)") (class "Default")
      (node (ref "R8") (pin "2") (pinfunction "2_2") (pintype "passive"))
      (node (ref "XS2") (pin "4") (pinfunction "NC_4") (pintype "passive"))
    )
    (net (code "68") (name "Net-(R9-Pad2)") (class "Default")
      (node (ref "R9") (pin "2") (pinfunction "2_2") (pintype "passive"))
      (node (ref "XS2") (pin "8") (pinfunction "NC_8") (pintype "passive"))
    )
    (net (code "69") (name "Net-(R10-Pad2)") (class "Default")
      (node (ref "R10") (pin "2") (pinfunction "2_2") (pintype "passive"))
      (node (ref "XS2") (pin "7") (pinfunction "NC_7") (pintype "passive"))
    )
    (net (code "70") (name "Net-(R11-Pad2)") (class "Default")
      (node (ref "R11") (pin "2") (pinfunction "2_2") (pintype "passive"))
      (node (ref "XS2") (pin "5") (pinfunction "NC_5") (pintype "passive"))
    )
    (net (code "71") (name "Net-(R14-Pad1)") (class "Default")
      (node (ref "R14") (pin "1") (pinfunction "1_1") (pintype "passive"))
      (node (ref "R15") (pin "2") (pinfunction "2_2") (pintype "passive"))
      (node (ref "RK") (pin "2") (pinfunction "2_2") (pintype "passive"))
    )
    (net (code "72") (name "Net-(U1-PWDN)") (class "Default")
      (node (ref "R1") (pin "2") (pinfunction "2_2") (pintype "passive"))
      (node (ref "U1") (pin "B6") (pinfunction "PWDN_B6") (pintype "passive"))
    )
    (net (code "73") (name "Net-(VD1-A)") (class "Default")
      (node (ref "R19") (pin "2") (pinfunction "2_2") (pintype "passive"))
      (node (ref "VD1") (pin "1") (pinfunction "A_1") (pintype "passive"))
    )
    (net (code "74") (name "unconnected-(DD1-PA0-Pad23)") (class "Default")
      (node (ref "DD1") (pin "23") (pinfunction "PA0_23") (pintype "passive"))
    )
    (net (code "75") (name "unconnected-(DD1-PA3-Pad26)") (class "Default")
      (node (ref "DD1") (pin "26") (pinfunction "PA3_26") (pintype "passive"))
    )
    (net (code "76") (name "unconnected-(DD1-PA5-Pad30)") (class "Default")
      (node (ref "DD1") (pin "30") (pinfunction "PA5_30") (pintype "passive"))
    )
    (net (code "77") (name "unconnected-(DD1-PA8-Pad67)") (class "Default")
      (node (ref "DD1") (pin "67") (pinfunction "PA8_67") (pintype "passive"))
    )
    (net (code "78") (name "unconnected-(DD1-PA11-Pad70)") (class "Default")
      (node (ref "DD1") (pin "70") (pinfunction "PA11_70") (pintype "passive"))
    )
    (net (code "79") (name "unconnected-(DD1-PA12-Pad71)") (class "Default")
      (node (ref "DD1") (pin "71") (pinfunction "PA12_71") (pintype "passive"))
    )
    (net (code "80") (name "unconnected-(DD1-PA15-Pad77)") (class "Default")
      (node (ref "DD1") (pin "77") (pinfunction "PA15_77") (pintype "passive"))
    )
    (net (code "81") (name "unconnected-(DD1-PB0-Pad35)") (class "Default")
      (node (ref "DD1") (pin "35") (pinfunction "PB0_35") (pintype "passive"))
    )
    (net (code "82") (name "unconnected-(DD1-PB1-Pad36)") (class "Default")
      (node (ref "DD1") (pin "36") (pinfunction "PB1_36") (pintype "passive"))
    )
    (net (code "83") (name "unconnected-(DD1-PB3-Pad89)") (class "Default")
      (node (ref "DD1") (pin "89") (pinfunction "PB3_89") (pintype "passive"))
    )
    (net (code "84") (name "unconnected-(DD1-PB4-Pad90)") (class "Default")
      (node (ref "DD1") (pin "90") (pinfunction "PB4_90") (pintype "passive"))
    )
    (net (code "85") (name "unconnected-(DD1-PB5-Pad91)") (class "Default")
      (node (ref "DD1") (pin "91") (pinfunction "PB5_91") (pintype "passive"))
    )
    (net (code "86") (name "unconnected-(DD1-PB10-Pad47)") (class "Default")
      (node (ref "DD1") (pin "47") (pinfunction "PB10_47") (pintype "passive"))
    )
    (net (code "87") (name "unconnected-(DD1-PB14-Pad53)") (class "Default")
      (node (ref "DD1") (pin "53") (pinfunction "PB14_53") (pintype "passive"))
    )
    (net (code "88") (name "unconnected-(DD1-PB15-Pad54)") (class "Default")
      (node (ref "DD1") (pin "54") (pinfunction "PB15_54") (pintype "passive"))
    )
    (net (code "89") (name "unconnected-(DD1-PC0-Pad15)") (class "Default")
      (node (ref "DD1") (pin "15") (pinfunction "PC0_15") (pintype "passive"))
    )
    (net (code "90") (name "unconnected-(DD1-PC2-Pad17)") (class "Default")
      (node (ref "DD1") (pin "17") (pinfunction "PC2_17") (pintype "passive"))
    )
    (net (code "91") (name "unconnected-(DD1-PC3-Pad18)") (class "Default")
      (node (ref "DD1") (pin "18") (pinfunction "PC3_18") (pintype "passive"))
    )
    (net (code "92") (name "unconnected-(DD1-PC8-Pad65)") (class "Default")
      (node (ref "DD1") (pin "65") (pinfunction "PC8_65") (pintype "passive"))
    )
    (net (code "93") (name "unconnected-(DD1-PC9-Pad66)") (class "Default")
      (node (ref "DD1") (pin "66") (pinfunction "PC9_66") (pintype "passive"))
    )
    (net (code "94") (name "unconnected-(DD1-PC10-Pad78)") (class "Default")
      (node (ref "DD1") (pin "78") (pinfunction "PC10_78") (pintype "passive"))
    )
    (net (code "95") (name "unconnected-(DD1-PC11-Pad79)") (class "Default")
      (node (ref "DD1") (pin "79") (pinfunction "PC11_79") (pintype "passive"))
    )
    (net (code "96") (name "unconnected-(DD1-PC12-Pad80)") (class "Default")
      (node (ref "DD1") (pin "80") (pinfunction "PC12_80") (pintype "passive"))
    )
    (net (code "97") (name "unconnected-(DD1-PC14-Pad8)") (class "Default")
      (node (ref "DD1") (pin "8") (pinfunction "PC14_8") (pintype "passive"))
    )
    (net (code "98") (name "unconnected-(DD1-PC15-Pad9)") (class "Default")
      (node (ref "DD1") (pin "9") (pinfunction "PC15_9") (pintype "passive"))
    )
    (net (code "99") (name "unconnected-(DD1-PD0-Pad81)") (class "Default")
      (node (ref "DD1") (pin "81") (pinfunction "PD0_81") (pintype "passive"))
    )
    (net (code "100") (name "unconnected-(DD1-PD1-Pad82)") (class "Default")
      (node (ref "DD1") (pin "82") (pinfunction "PD1_82") (pintype "passive"))
    )
    (net (code "101") (name "unconnected-(DD1-PD2-Pad83)") (class "Default")
      (node (ref "DD1") (pin "83") (pinfunction "PD2_83") (pintype "passive"))
    )
    (net (code "102") (name "unconnected-(DD1-PD4-Pad85)") (class "Default")
      (node (ref "DD1") (pin "85") (pinfunction "PD4_85") (pintype "passive"))
    )
    (net (code "103") (name "unconnected-(DD1-PD5-Pad86)") (class "Default")
      (node (ref "DD1") (pin "86") (pinfunction "PD5_86") (pintype "passive"))
    )
    (net (code "104") (name "unconnected-(DD1-PD6-Pad87)") (class "Default")
      (node (ref "DD1") (pin "87") (pinfunction "PD6_87") (pintype "passive"))
    )
    (net (code "105") (name "unconnected-(DD1-PD7-Pad88)") (class "Default")
      (node (ref "DD1") (pin "88") (pinfunction "PD7_88") (pintype "passive"))
    )
    (net (code "106") (name "unconnected-(DD1-PD8-Pad55)") (class "Default")
      (node (ref "DD1") (pin "55") (pinfunction "PD8_55") (pintype "passive"))
    )
    (net (code "107") (name "unconnected-(DD1-PD9-Pad56)") (class "Default")
      (node (ref "DD1") (pin "56") (pinfunction "PD9_56") (pintype "passive"))
    )
    (net (code "108") (name "unconnected-(DD1-PD10-Pad57)") (class "Default")
      (node (ref "DD1") (pin "57") (pinfunction "PD10_57") (pintype "passive"))
    )
    (net (code "109") (name "unconnected-(DD1-PD11-Pad58)") (class "Default")
      (node (ref "DD1") (pin "58") (pinfunction "PD11_58") (pintype "passive"))
    )
    (net (code "110") (name "unconnected-(DD1-PD12-Pad59)") (class "Default")
      (node (ref "DD1") (pin "59") (pinfunction "PD12_59") (pintype "passive"))
    )
    (net (code "111") (name "unconnected-(DD1-PD13-Pad60)") (class "Default")
      (node (ref "DD1") (pin "60") (pinfunction "PD13_60") (pintype "passive"))
    )
    (net (code "112") (name "unconnected-(DD1-PD14-Pad61)") (class "Default")
      (node (ref "DD1") (pin "61") (pinfunction "PD14_61") (pintype "passive"))
    )
    (net (code "113") (name "unconnected-(DD1-PD15-Pad62)") (class "Default")
      (node (ref "DD1") (pin "62") (pinfunction "PD15_62") (pintype "passive"))
    )
    (net (code "114") (name "unconnected-(DD1-PE2-Pad1)") (class "Default")
      (node (ref "DD1") (pin "1") (pinfunction "PE2_1") (pintype "passive"))
    )
    (net (code "115") (name "unconnected-(DD1-PE3-Pad2)") (class "Default")
      (node (ref "DD1") (pin "2") (pinfunction "PE3_2") (pintype "passive"))
    )
    (net (code "116") (name "unconnected-(DD1-PE7-Pad38)") (class "Default")
      (node (ref "DD1") (pin "38") (pinfunction "PE7_38") (pintype "passive"))
    )
    (net (code "117") (name "unconnected-(DD1-PE8-Pad39)") (class "Default")
      (node (ref "DD1") (pin "39") (pinfunction "PE8_39") (pintype "passive"))
    )
    (net (code "118") (name "unconnected-(DD1-PE9-Pad40)") (class "Default")
      (node (ref "DD1") (pin "40") (pinfunction "PE9_40") (pintype "passive"))
    )
    (net (code "119") (name "unconnected-(DD1-PE10-Pad41)") (class "Default")
      (node (ref "DD1") (pin "41") (pinfunction "PE10_41") (pintype "passive"))
    )
    (net (code "120") (name "unconnected-(DD1-PE11-Pad42)") (class "Default")
      (node (ref "DD1") (pin "42") (pinfunction "PE11_42") (pintype "passive"))
    )
    (net (code "121") (name "unconnected-(DD1-PE12-Pad43)") (class "Default")
      (node (ref "DD1") (pin "43") (pinfunction "PE12_43") (pintype "passive"))
    )
    (net (code "122") (name "unconnected-(DD1-PE13-Pad44)") (class "Default")
      (node (ref "DD1") (pin "44") (pinfunction "PE13_44") (pintype "passive"))
    )
    (net (code "123") (name "unconnected-(DD1-PE14-Pad45)") (class "Default")
      (node (ref "DD1") (pin "45") (pinfunction "PE14_45") (pintype "passive"))
    )
    (net (code "124") (name "unconnected-(DD1-PE15-Pad46)") (class "Default")
      (node (ref "DD1") (pin "46") (pinfunction "PE15_46") (pintype "passive"))
    )
    (net (code "125") (name "unconnected-(DD1-VDDA-Pad22)") (class "Default")
      (node (ref "DD1") (pin "22") (pinfunction "VDDA_22") (pintype "passive"))
    )
    (net (code "126") (name "unconnected-(DD1-VREF+-Pad21)") (class "Default")
      (node (ref "DD1") (pin "21") (pinfunction "VREF+_21") (pintype "passive"))
    )
    (net (code "127") (name "unconnected-(DD2-RXER{slash}~{PHYAD0}-Pad10)") (class "Default")
      (node (ref "DD2") (pin "10") (pinfunction "RXER/~{PHYAD0}_10") (pintype "passive"))
    )
    (net (code "128") (name "unconnected-(DD2-VSS-Pad25)") (class "Default")
      (node (ref "DD2") (pin "25") (pinfunction "VSS_25") (pintype "passive"))
    )
    (net (code "129") (name "unconnected-(DD3-PMID-Pad23)") (class "Default")
      (node (ref "DD3") (pin "23") (pinfunction "PMID_23") (pintype "passive"))
    )
    (net (code "130") (name "unconnected-(DD3-~{CE}-Pad9)") (class "Default")
      (node (ref "DD3") (pin "9") (pinfunction "~{CE}_9") (pintype "passive"))
    )
    (net (code "131") (name "unconnected-(U1-DGND_1-PadE6)") (class "Default")
      (node (ref "U1") (pin "E6") (pinfunction "DGND_1_E6") (pintype "passive"))
    )
    (net (code "132") (name "unconnected-(U1-DGND_2-PadG2)") (class "Default")
      (node (ref "U1") (pin "G2") (pinfunction "DGND_2_G2") (pintype "passive"))
    )
    (net (code "133") (name "unconnected-(U1-DVDD_1-PadF2)") (class "Default")
      (node (ref "U1") (pin "F2") (pinfunction "DVDD_1_F2") (pintype "passive"))
    )
    (net (code "134") (name "unconnected-(U1-DVDD_2-PadF6)") (class "Default")
      (node (ref "U1") (pin "F6") (pinfunction "DVDD_2_F6") (pintype "passive"))
    )
    (net (code "135") (name "unconnected-(U1-EGND-PadE4)") (class "Default")
      (node (ref "U1") (pin "E4") (pinfunction "EGND_E4") (pintype "passive"))
    )
    (net (code "136") (name "unconnected-(U1-EVDD_1-PadF1)") (class "Default")
      (node (ref "U1") (pin "F1") (pinfunction "EVDD_1_F1") (pintype "passive"))
    )
    (net (code "137") (name "unconnected-(U1-EVDD_2-PadG1)") (class "Default")
      (node (ref "U1") (pin "G1") (pinfunction "EVDD_2_G1") (pintype "passive"))
    )
    (net (code "138") (name "unconnected-(U1-EXPST_B-PadA2)") (class "Default")
      (node (ref "U1") (pin "A2") (pinfunction "EXPST_B_A2") (pintype "passive"))
    )
    (net (code "139") (name "unconnected-(U1-FREX-PadB2)") (class "Default")
      (node (ref "U1") (pin "B2") (pinfunction "FREX_B2") (pintype "passive"))
    )
    (net (code "140") (name "unconnected-(U1-NC-PadD6)") (class "Default")
      (node (ref "U1") (pin "D6") (pinfunction "NC_D6") (pintype "passive"))
    )
    (net (code "141") (name "unconnected-(U1-RESETB-PadC6)") (class "Default")
      (node (ref "U1") (pin "C6") (pinfunction "RESETB_C6") (pintype "passive"))
    )
    (net (code "142") (name "unconnected-(U1-SGND-PadA4)") (class "Default")
      (node (ref "U1") (pin "A4") (pinfunction "SGND_A4") (pintype "passive"))
    )
    (net (code "143") (name "unconnected-(U1-STROBE-PadA6)") (class "Default")
      (node (ref "U1") (pin "A6") (pinfunction "STROBE_A6") (pintype "passive"))
    )
    (net (code "144") (name "unconnected-(U1-SVDD_1-PadB4)") (class "Default")
      (node (ref "U1") (pin "B4") (pinfunction "SVDD_1_B4") (pintype "passive"))
    )
    (net (code "145") (name "unconnected-(U1-SVDD_2-PadB5)") (class "Default")
      (node (ref "U1") (pin "B5") (pinfunction "SVDD_2_B5") (pintype "passive"))
    )
    (net (code "146") (name "unconnected-(U1-VREFH-PadC5)") (class "Default")
      (node (ref "U1") (pin "C5") (pinfunction "VREFH_C5") (pintype "passive"))
    )
    (net (code "147") (name "unconnected-(U1-VREFN-PadA5)") (class "Default")
      (node (ref "U1") (pin "A5") (pinfunction "VREFN_A5") (pintype "passive"))
    )
    (net (code "148") (name "unconnected-(U1-Y0-PadE2)") (class "Default")
      (node (ref "U1") (pin "E2") (pinfunction "Y0_E2") (pintype "passive"))
    )
    (net (code "149") (name "unconnected-(U1-Y1-PadE1)") (class "Default")
      (node (ref "U1") (pin "E1") (pinfunction "Y1_E1") (pintype "passive"))
    )
  )
)
